# PT_V2.net
KiCad netlist of a schematic drawn in EAGLE
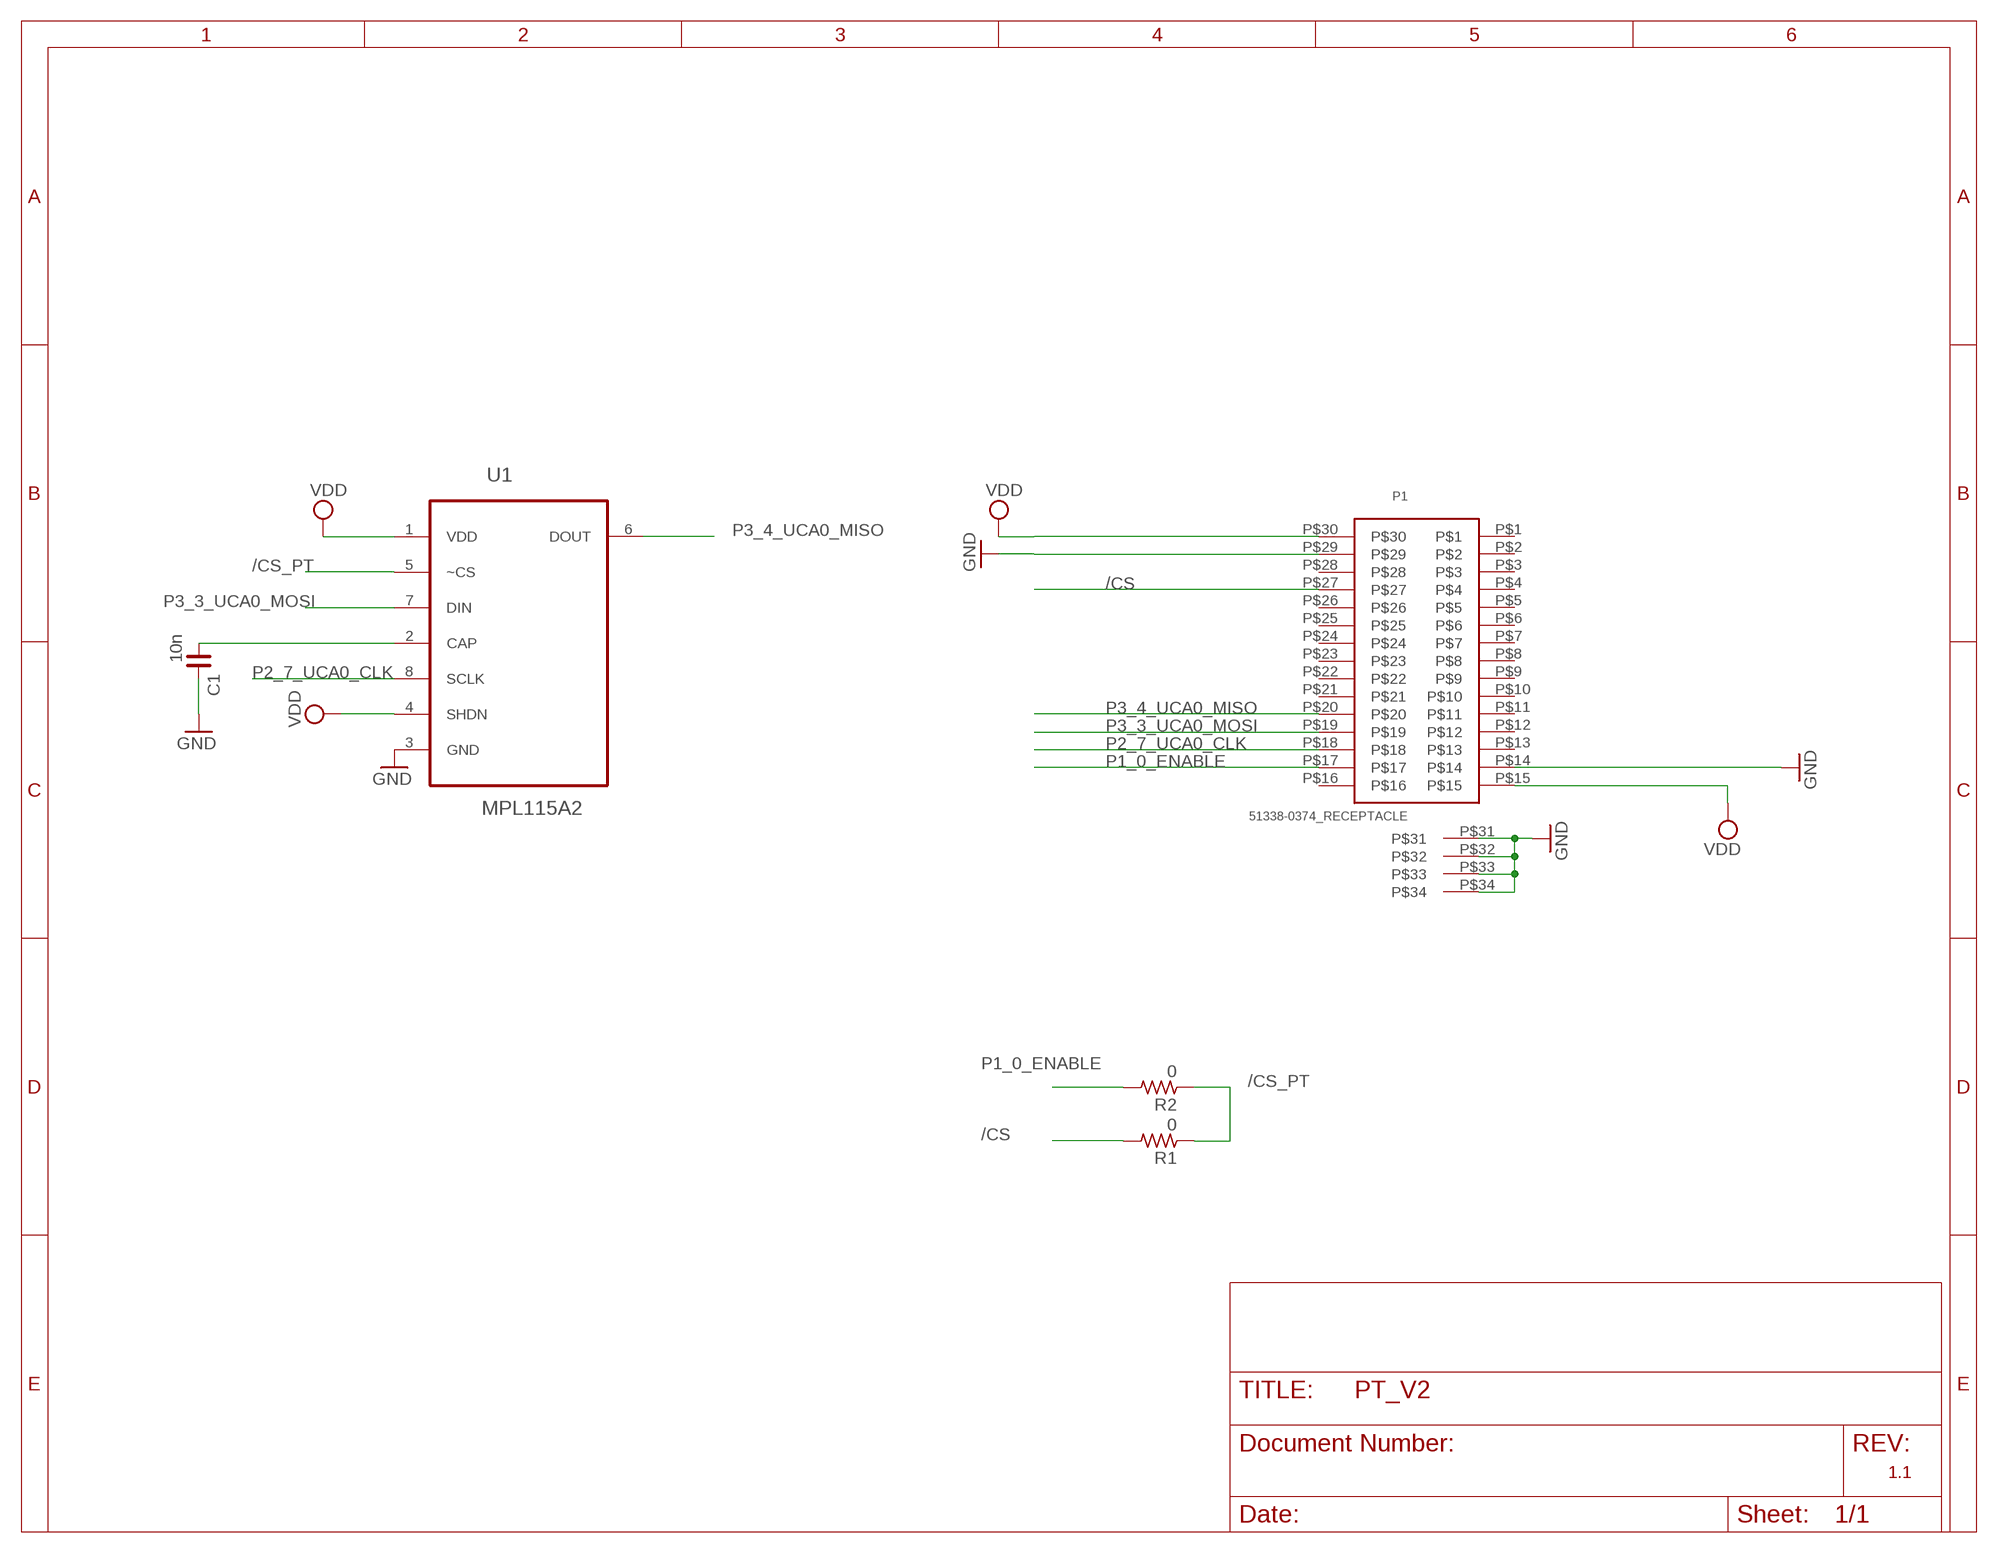
[diagram p0: schematic, sheet 1]

(export (version "E")
  (design (tool "Eeschema 10.0.6"))
  (components
    (comp (ref "C1")
      (value "10n")
      (footprint "eagle-import:C0402")
      (libsource (lib "eagle-import") (part "C_0402"))
    )
    (comp (ref "P1")
      (value "51338-0374_RECEPTACLE")
      (footprint "eagle-import:51338-0374_RECEPTACLE")
      (libsource (lib "eagle-import") (part "51338-0374_RECEPTACLE"))
    )
    (comp (ref "R1")
      (value "0")
      (footprint "eagle-import:R0402")
      (libsource (lib "eagle-import") (part "R_0402"))
    )
    (comp (ref "R2")
      (value "0")
      (footprint "eagle-import:R0402")
      (libsource (lib "eagle-import") (part "R_0402"))
    )
    (comp (ref "U1")
      (value "MPL115A2")
      (footprint "eagle-import:LGA8R125P0X4_500X300X120")
      (libsource (lib "eagle-import") (part "MPL115A2"))
    )
  )
  (nets
    (net (code "1") (name "/P1_0_ENABLE") (class "Default")
      (node (ref "P1") (pin "P$17") (pinfunction "P$17_P$17") (pintype "bidirectional"))
      (node (ref "R2") (pin "2") (pinfunction "2_2") (pintype "passive"))
    )
    (net (code "2") (name "/P2_7_UCA0_CLK") (class "Default")
      (node (ref "P1") (pin "P$18") (pinfunction "P$18_P$18") (pintype "bidirectional"))
      (node (ref "U1") (pin "8") (pinfunction "SCLK_8") (pintype "input"))
    )
    (net (code "3") (name "/P3_3_UCA0_MOSI") (class "Default")
      (node (ref "P1") (pin "P$19") (pinfunction "P$19_P$19") (pintype "bidirectional"))
      (node (ref "U1") (pin "7") (pinfunction "DIN_7") (pintype "input"))
    )
    (net (code "4") (name "/P3_4_UCA0_MISO") (class "Default")
      (node (ref "P1") (pin "P$20") (pinfunction "P$20_P$20") (pintype "bidirectional"))
      (node (ref "U1") (pin "6") (pinfunction "DOUT_6") (pintype "output"))
    )
    (net (code "5") (name "/{slash}CS") (class "Default")
      (node (ref "P1") (pin "P$27") (pinfunction "P$27_P$27") (pintype "bidirectional"))
      (node (ref "R1") (pin "2") (pinfunction "2_2") (pintype "passive"))
    )
    (net (code "6") (name "/{slash}CS_PT") (class "Default")
      (node (ref "R1") (pin "1") (pinfunction "1_1") (pintype "passive"))
      (node (ref "R2") (pin "1") (pinfunction "1_1") (pintype "passive"))
      (node (ref "U1") (pin "5") (pinfunction "~{CS}_5") (pintype "input"))
    )
    (net (code "7") (name "GND") (class "Default")
      (node (ref "C1") (pin "2") (pinfunction "2_2") (pintype "passive"))
      (node (ref "P1") (pin "P$14") (pinfunction "P$14_P$14") (pintype "bidirectional"))
      (node (ref "P1") (pin "P$29") (pinfunction "P$29_P$29") (pintype "bidirectional"))
      (node (ref "P1") (pin "P$31") (pinfunction "P$31_P$31") (pintype "bidirectional"))
      (node (ref "P1") (pin "P$32") (pinfunction "P$32_P$32") (pintype "bidirectional"))
      (node (ref "P1") (pin "P$33") (pinfunction "P$33_P$33") (pintype "bidirectional"))
      (node (ref "P1") (pin "P$34") (pinfunction "P$34_P$34") (pintype "bidirectional"))
      (node (ref "U1") (pin "3") (pinfunction "GND_3") (pintype "passive"))
    )
    (net (code "8") (name "Net-(U1-CAP)") (class "Default")
      (node (ref "C1") (pin "1") (pinfunction "1_1") (pintype "passive"))
      (node (ref "U1") (pin "2") (pinfunction "CAP_2") (pintype "input"))
    )
    (net (code "9") (name "VDD") (class "Default")
      (node (ref "P1") (pin "P$15") (pinfunction "P$15_P$15") (pintype "bidirectional"))
      (node (ref "P1") (pin "P$30") (pinfunction "P$30_P$30") (pintype "bidirectional"))
      (node (ref "U1") (pin "1") (pinfunction "VDD_1") (pintype "power_in"))
      (node (ref "U1") (pin "4") (pinfunction "SHDN_4") (pintype "input"))
    )
    (net (code "10") (name "unconnected-(P1-PadP$1)") (class "Default")
      (node (ref "P1") (pin "P$1") (pinfunction "P$1_P$1") (pintype "bidirectional"))
    )
    (net (code "11") (name "unconnected-(P1-PadP$2)") (class "Default")
      (node (ref "P1") (pin "P$2") (pinfunction "P$2_P$2") (pintype "bidirectional"))
    )
    (net (code "12") (name "unconnected-(P1-PadP$3)") (class "Default")
      (node (ref "P1") (pin "P$3") (pinfunction "P$3_P$3") (pintype "bidirectional"))
    )
    (net (code "13") (name "unconnected-(P1-PadP$4)") (class "Default")
      (node (ref "P1") (pin "P$4") (pinfunction "P$4_P$4") (pintype "bidirectional"))
    )
    (net (code "14") (name "unconnected-(P1-PadP$5)") (class "Default")
      (node (ref "P1") (pin "P$5") (pinfunction "P$5_P$5") (pintype "bidirectional"))
    )
    (net (code "15") (name "unconnected-(P1-PadP$6)") (class "Default")
      (node (ref "P1") (pin "P$6") (pinfunction "P$6_P$6") (pintype "bidirectional"))
    )
    (net (code "16") (name "unconnected-(P1-PadP$7)") (class "Default")
      (node (ref "P1") (pin "P$7") (pinfunction "P$7_P$7") (pintype "bidirectional"))
    )
    (net (code "17") (name "unconnected-(P1-PadP$8)") (class "Default")
      (node (ref "P1") (pin "P$8") (pinfunction "P$8_P$8") (pintype "bidirectional"))
    )
    (net (code "18") (name "unconnected-(P1-PadP$9)") (class "Default")
      (node (ref "P1") (pin "P$9") (pinfunction "P$9_P$9") (pintype "bidirectional"))
    )
    (net (code "19") (name "unconnected-(P1-PadP$10)") (class "Default")
      (node (ref "P1") (pin "P$10") (pinfunction "P$10_P$10") (pintype "bidirectional"))
    )
    (net (code "20") (name "unconnected-(P1-PadP$11)") (class "Default")
      (node (ref "P1") (pin "P$11") (pinfunction "P$11_P$11") (pintype "bidirectional"))
    )
    (net (code "21") (name "unconnected-(P1-PadP$12)") (class "Default")
      (node (ref "P1") (pin "P$12") (pinfunction "P$12_P$12") (pintype "bidirectional"))
    )
    (net (code "22") (name "unconnected-(P1-PadP$13)") (class "Default")
      (node (ref "P1") (pin "P$13") (pinfunction "P$13_P$13") (pintype "bidirectional"))
    )
    (net (code "23") (name "unconnected-(P1-PadP$16)") (class "Default")
      (node (ref "P1") (pin "P$16") (pinfunction "P$16_P$16") (pintype "bidirectional"))
    )
    (net (code "24") (name "unconnected-(P1-PadP$21)") (class "Default")
      (node (ref "P1") (pin "P$21") (pinfunction "P$21_P$21") (pintype "bidirectional"))
    )
    (net (code "25") (name "unconnected-(P1-PadP$22)") (class "Default")
      (node (ref "P1") (pin "P$22") (pinfunction "P$22_P$22") (pintype "bidirectional"))
    )
    (net (code "26") (name "unconnected-(P1-PadP$23)") (class "Default")
      (node (ref "P1") (pin "P$23") (pinfunction "P$23_P$23") (pintype "bidirectional"))
    )
    (net (code "27") (name "unconnected-(P1-PadP$24)") (class "Default")
      (node (ref "P1") (pin "P$24") (pinfunction "P$24_P$24") (pintype "bidirectional"))
    )
    (net (code "28") (name "unconnected-(P1-PadP$25)") (class "Default")
      (node (ref "P1") (pin "P$25") (pinfunction "P$25_P$25") (pintype "bidirectional"))
    )
    (net (code "29") (name "unconnected-(P1-PadP$26)") (class "Default")
      (node (ref "P1") (pin "P$26") (pinfunction "P$26_P$26") (pintype "bidirectional"))
    )
    (net (code "30") (name "unconnected-(P1-PadP$28)") (class "Default")
      (node (ref "P1") (pin "P$28") (pinfunction "P$28_P$28") (pintype "bidirectional"))
    )
  )
)
